# Filtre_Seulement.net
KiCad netlist of a schematic drawn in Altium Designer
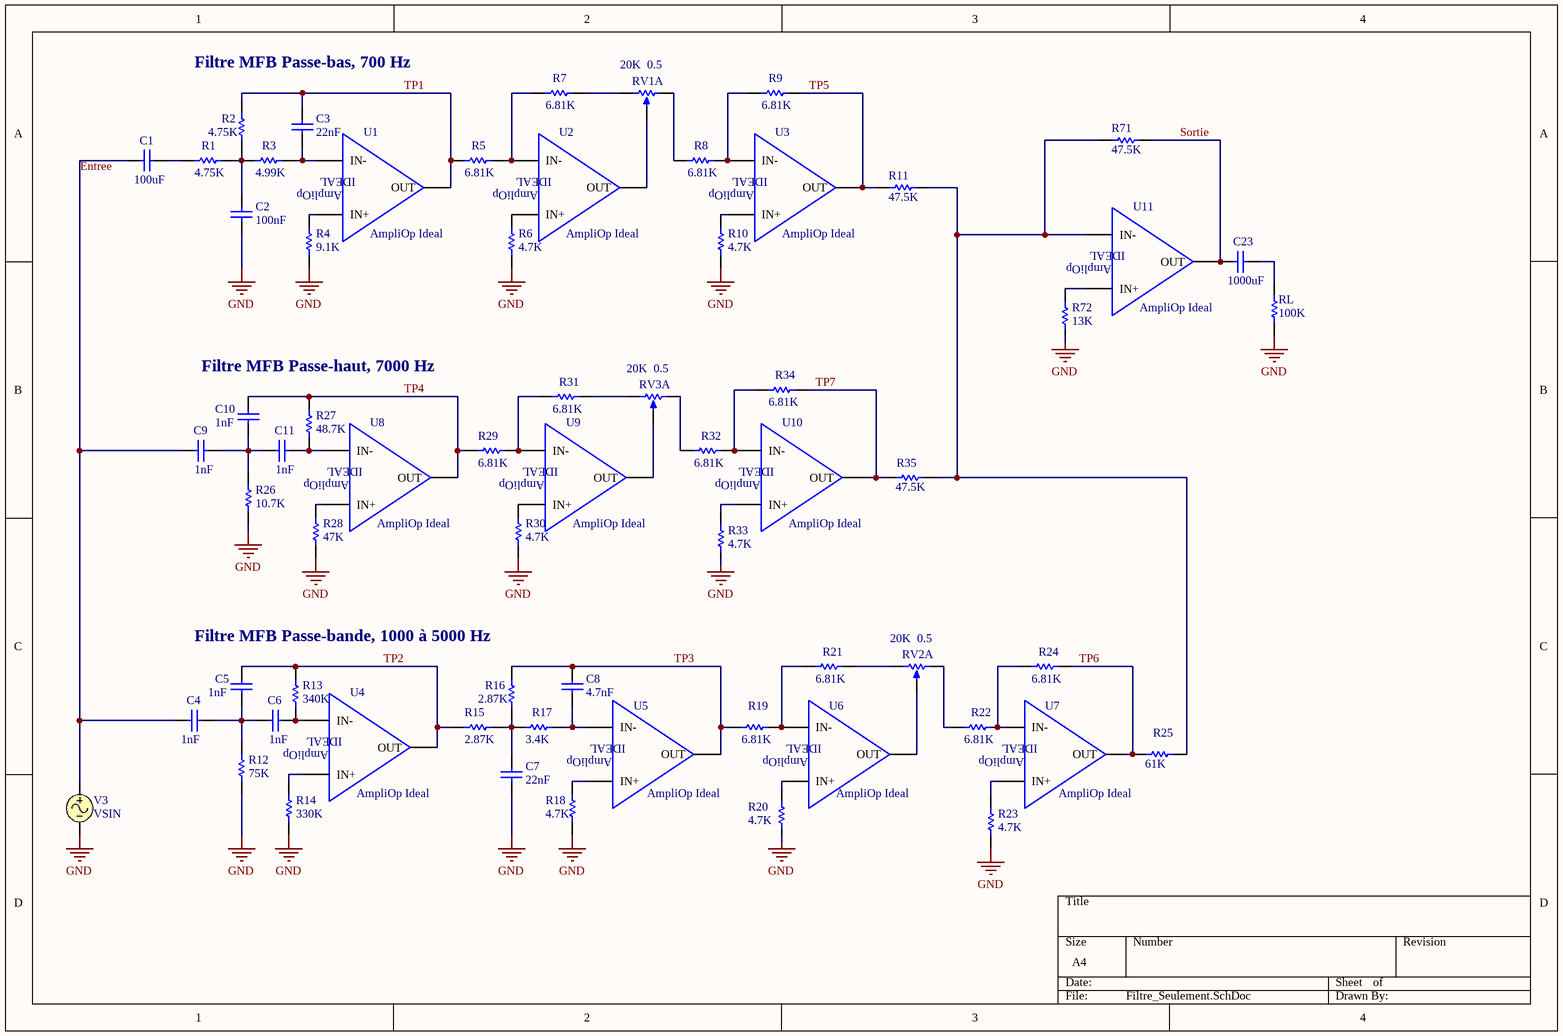
[diagram p0: Filtre_Seulement.SchDoc]

(export (version "E")
  (design (tool "Eeschema 10.0.6"))
  (components
    (comp (ref "C1")
      (value "100uF")
      (footprint "RAD-0.3")
      (description "Capacitor")
      (fields (field (name "Comment") "Cap") (field (name "PUBLISHER") "Altium Limited"))
      (libsource (lib "Miscellaneous Devices") (part "Cap"))
    )
    (comp (ref "C2")
      (value "100nF")
      (footprint "RAD-0.3")
      (description "Capacitor")
      (fields (field (name "Comment") "Cap") (field (name "PUBLISHER") "Altium Limited"))
      (libsource (lib "Miscellaneous Devices") (part "Cap"))
    )
    (comp (ref "C3")
      (value "22nF")
      (footprint "RAD-0.3")
      (description "Capacitor")
      (fields (field (name "Comment") "Cap") (field (name "PUBLISHER") "Altium Limited"))
      (libsource (lib "Miscellaneous Devices") (part "Cap"))
    )
    (comp (ref "C4")
      (value "1nF")
      (footprint "RAD-0.3")
      (description "Capacitor")
      (fields (field (name "Comment") "Cap") (field (name "PUBLISHER") "Altium Limited"))
      (libsource (lib "Miscellaneous Devices") (part "Cap"))
    )
    (comp (ref "C5")
      (value "1nF")
      (footprint "RAD-0.3")
      (description "Capacitor")
      (fields (field (name "Comment") "Cap") (field (name "PUBLISHER") "Altium Limited"))
      (libsource (lib "Miscellaneous Devices") (part "Cap"))
    )
    (comp (ref "C6")
      (value "1nF")
      (footprint "RAD-0.3")
      (description "Capacitor")
      (fields (field (name "Comment") "Cap") (field (name "PUBLISHER") "Altium Limited"))
      (libsource (lib "Miscellaneous Devices") (part "Cap"))
    )
    (comp (ref "C7")
      (value "22nF")
      (footprint "RAD-0.3")
      (description "Capacitor")
      (fields (field (name "Comment") "Cap") (field (name "PUBLISHER") "Altium Limited"))
      (libsource (lib "Miscellaneous Devices") (part "Cap"))
    )
    (comp (ref "C8")
      (value "4.7nF")
      (footprint "RAD-0.3")
      (description "Capacitor")
      (fields (field (name "Comment") "Cap") (field (name "PUBLISHER") "Altium Limited"))
      (libsource (lib "Miscellaneous Devices") (part "Cap"))
    )
    (comp (ref "C9")
      (value "1nF")
      (footprint "RAD-0.3")
      (description "Capacitor")
      (fields (field (name "Comment") "Cap") (field (name "PUBLISHER") "Altium Limited"))
      (libsource (lib "Miscellaneous Devices") (part "Cap"))
    )
    (comp (ref "C10")
      (value "1nF")
      (footprint "RAD-0.3")
      (description "Capacitor")
      (fields (field (name "Comment") "Cap") (field (name "PUBLISHER") "Altium Limited"))
      (libsource (lib "Miscellaneous Devices") (part "Cap"))
    )
    (comp (ref "C11")
      (value "1nF")
      (footprint "RAD-0.3")
      (description "Capacitor")
      (fields (field (name "Comment") "Cap") (field (name "PUBLISHER") "Altium Limited"))
      (libsource (lib "Miscellaneous Devices") (part "Cap"))
    )
    (comp (ref "C23")
      (value "1000uF")
      (footprint "RAD-0.3")
      (description "Capacitor")
      (fields (field (name "Comment") "Cap") (field (name "PUBLISHER") "Altium Limited"))
      (libsource (lib "Miscellaneous Devices") (part "Cap"))
    )
    (comp (ref "R1")
      (value "4.75K")
      (footprint "AXIAL-0.3")
      (description "Resistor")
      (fields (field (name "Comment") "Res1") (field (name "PUBLISHER") "Altium Limited"))
      (libsource (lib "Miscellaneous Devices") (part "Res1"))
    )
    (comp (ref "R2")
      (value "4.75K")
      (footprint "AXIAL-0.3")
      (description "Resistor")
      (fields (field (name "Comment") "Res1") (field (name "PUBLISHER") "Altium Limited"))
      (libsource (lib "Miscellaneous Devices") (part "Res1"))
    )
    (comp (ref "R3")
      (value "4.99K")
      (footprint "AXIAL-0.3")
      (description "Resistor")
      (fields (field (name "Comment") "Res1") (field (name "PUBLISHER") "Altium Limited"))
      (libsource (lib "Miscellaneous Devices") (part "Res1"))
    )
    (comp (ref "R4")
      (value "9.1K")
      (footprint "AXIAL-0.3")
      (description "Resistor")
      (fields (field (name "Comment") "Res1") (field (name "PUBLISHER") "Altium Limited"))
      (libsource (lib "Miscellaneous Devices") (part "Res1"))
    )
    (comp (ref "R5")
      (value "6.81K")
      (footprint "AXIAL-0.3")
      (description "Resistor")
      (fields (field (name "Comment") "Res1") (field (name "PUBLISHER") "Altium Limited"))
      (libsource (lib "Miscellaneous Devices") (part "Res1"))
    )
    (comp (ref "R6")
      (value "4.7K")
      (footprint "AXIAL-0.3")
      (description "Resistor")
      (fields (field (name "Comment") "Res1") (field (name "PUBLISHER") "Altium Limited"))
      (libsource (lib "Miscellaneous Devices") (part "Res1"))
    )
    (comp (ref "R7")
      (value "6.81K")
      (footprint "AXIAL-0.3")
      (description "Resistor")
      (fields (field (name "Comment") "Res1") (field (name "PUBLISHER") "Altium Limited"))
      (libsource (lib "Miscellaneous Devices") (part "Res1"))
    )
    (comp (ref "R8")
      (value "6.81K")
      (footprint "AXIAL-0.3")
      (description "Resistor")
      (fields (field (name "Comment") "Res1") (field (name "PUBLISHER") "Altium Limited"))
      (libsource (lib "Miscellaneous Devices") (part "Res1"))
    )
    (comp (ref "R9")
      (value "6.81K")
      (footprint "AXIAL-0.3")
      (description "Resistor")
      (fields (field (name "Comment") "Res1") (field (name "PUBLISHER") "Altium Limited"))
      (libsource (lib "Miscellaneous Devices") (part "Res1"))
    )
    (comp (ref "R10")
      (value "4.7K")
      (footprint "AXIAL-0.3")
      (description "Resistor")
      (fields (field (name "Comment") "Res1") (field (name "PUBLISHER") "Altium Limited"))
      (libsource (lib "Miscellaneous Devices") (part "Res1"))
    )
    (comp (ref "R11")
      (value "47.5K")
      (footprint "AXIAL-0.3")
      (description "Resistor")
      (fields (field (name "Comment") "Res1") (field (name "PUBLISHER") "Altium Limited"))
      (libsource (lib "Miscellaneous Devices") (part "Res1"))
    )
    (comp (ref "R12")
      (value "75K")
      (footprint "AXIAL-0.3")
      (description "Resistor")
      (fields (field (name "Comment") "Res1") (field (name "PUBLISHER") "Altium Limited"))
      (libsource (lib "Miscellaneous Devices") (part "Res1"))
    )
    (comp (ref "R13")
      (value "340K")
      (footprint "AXIAL-0.3")
      (description "Resistor")
      (fields (field (name "Comment") "Res1") (field (name "PUBLISHER") "Altium Limited"))
      (libsource (lib "Miscellaneous Devices") (part "Res1"))
    )
    (comp (ref "R14")
      (value "330K")
      (footprint "AXIAL-0.3")
      (description "Resistor")
      (fields (field (name "Comment") "Res1") (field (name "PUBLISHER") "Altium Limited"))
      (libsource (lib "Miscellaneous Devices") (part "Res1"))
    )
    (comp (ref "R15")
      (value "2.87K")
      (footprint "AXIAL-0.3")
      (description "Resistor")
      (fields (field (name "Comment") "Res1") (field (name "PUBLISHER") "Altium Limited"))
      (libsource (lib "Miscellaneous Devices") (part "Res1"))
    )
    (comp (ref "R16")
      (value "2.87K")
      (footprint "AXIAL-0.3")
      (description "Resistor")
      (fields (field (name "Comment") "Res1") (field (name "PUBLISHER") "Altium Limited"))
      (libsource (lib "Miscellaneous Devices") (part "Res1"))
    )
    (comp (ref "R17")
      (value "3.4K")
      (footprint "AXIAL-0.3")
      (description "Resistor")
      (fields (field (name "Comment") "Res1") (field (name "PUBLISHER") "Altium Limited"))
      (libsource (lib "Miscellaneous Devices") (part "Res1"))
    )
    (comp (ref "R18")
      (value "4.7K")
      (footprint "AXIAL-0.3")
      (description "Resistor")
      (fields (field (name "Comment") "Res1") (field (name "PUBLISHER") "Altium Limited"))
      (libsource (lib "Miscellaneous Devices") (part "Res1"))
    )
    (comp (ref "R19")
      (value "6.81K")
      (footprint "AXIAL-0.3")
      (description "Resistor")
      (fields (field (name "Comment") "Res1") (field (name "PUBLISHER") "Altium Limited"))
      (libsource (lib "Miscellaneous Devices") (part "Res1"))
    )
    (comp (ref "R20")
      (value "4.7K")
      (footprint "AXIAL-0.3")
      (description "Resistor")
      (fields (field (name "Comment") "Res1") (field (name "PUBLISHER") "Altium Limited"))
      (libsource (lib "Miscellaneous Devices") (part "Res1"))
    )
    (comp (ref "R21")
      (value "6.81K")
      (footprint "AXIAL-0.3")
      (description "Resistor")
      (fields (field (name "Comment") "Res1") (field (name "PUBLISHER") "Altium Limited"))
      (libsource (lib "Miscellaneous Devices") (part "Res1"))
    )
    (comp (ref "R22")
      (value "6.81K")
      (footprint "AXIAL-0.3")
      (description "Resistor")
      (fields (field (name "Comment") "Res1") (field (name "PUBLISHER") "Altium Limited"))
      (libsource (lib "Miscellaneous Devices") (part "Res1"))
    )
    (comp (ref "R23")
      (value "4.7K")
      (footprint "AXIAL-0.3")
      (description "Resistor")
      (fields (field (name "Comment") "Res1") (field (name "PUBLISHER") "Altium Limited"))
      (libsource (lib "Miscellaneous Devices") (part "Res1"))
    )
    (comp (ref "R24")
      (value "6.81K")
      (footprint "AXIAL-0.3")
      (description "Resistor")
      (fields (field (name "Comment") "Res1") (field (name "PUBLISHER") "Altium Limited"))
      (libsource (lib "Miscellaneous Devices") (part "Res1"))
    )
    (comp (ref "R25")
      (value "61K")
      (footprint "AXIAL-0.3")
      (description "Resistor")
      (fields (field (name "Comment") "Res1") (field (name "PUBLISHER") "Altium Limited"))
      (libsource (lib "Miscellaneous Devices") (part "Res1"))
    )
    (comp (ref "R26")
      (value "10.7K")
      (footprint "AXIAL-0.3")
      (description "Resistor")
      (fields (field (name "Comment") "Res1") (field (name "PUBLISHER") "Altium Limited"))
      (libsource (lib "Miscellaneous Devices") (part "Res1"))
    )
    (comp (ref "R27")
      (value "48.7K")
      (footprint "AXIAL-0.3")
      (description "Resistor")
      (fields (field (name "Comment") "Res1") (field (name "PUBLISHER") "Altium Limited"))
      (libsource (lib "Miscellaneous Devices") (part "Res1"))
    )
    (comp (ref "R28")
      (value "47K")
      (footprint "AXIAL-0.3")
      (description "Resistor")
      (fields (field (name "Comment") "Res1") (field (name "PUBLISHER") "Altium Limited"))
      (libsource (lib "Miscellaneous Devices") (part "Res1"))
    )
    (comp (ref "R29")
      (value "6.81K")
      (footprint "AXIAL-0.3")
      (description "Resistor")
      (fields (field (name "Comment") "Res1") (field (name "PUBLISHER") "Altium Limited"))
      (libsource (lib "Miscellaneous Devices") (part "Res1"))
    )
    (comp (ref "R30")
      (value "4.7K")
      (footprint "AXIAL-0.3")
      (description "Resistor")
      (fields (field (name "Comment") "Res1") (field (name "PUBLISHER") "Altium Limited"))
      (libsource (lib "Miscellaneous Devices") (part "Res1"))
    )
    (comp (ref "R31")
      (value "6.81K")
      (footprint "AXIAL-0.3")
      (description "Resistor")
      (fields (field (name "Comment") "Res1") (field (name "PUBLISHER") "Altium Limited"))
      (libsource (lib "Miscellaneous Devices") (part "Res1"))
    )
    (comp (ref "R32")
      (value "6.81K")
      (footprint "AXIAL-0.3")
      (description "Resistor")
      (fields (field (name "Comment") "Res1") (field (name "PUBLISHER") "Altium Limited"))
      (libsource (lib "Miscellaneous Devices") (part "Res1"))
    )
    (comp (ref "R33")
      (value "4.7K")
      (footprint "AXIAL-0.3")
      (description "Resistor")
      (fields (field (name "Comment") "Res1") (field (name "PUBLISHER") "Altium Limited"))
      (libsource (lib "Miscellaneous Devices") (part "Res1"))
    )
    (comp (ref "R34")
      (value "6.81K")
      (footprint "AXIAL-0.3")
      (description "Resistor")
      (fields (field (name "Comment") "Res1") (field (name "PUBLISHER") "Altium Limited"))
      (libsource (lib "Miscellaneous Devices") (part "Res1"))
    )
    (comp (ref "R35")
      (value "47.5K")
      (footprint "AXIAL-0.3")
      (description "Resistor")
      (fields (field (name "Comment") "Res1") (field (name "PUBLISHER") "Altium Limited"))
      (libsource (lib "Miscellaneous Devices") (part "Res1"))
    )
    (comp (ref "R71")
      (value "47.5K")
      (footprint "AXIAL-0.3")
      (description "Resistor")
      (fields (field (name "Comment") "Res1") (field (name "PUBLISHER") "Altium Limited"))
      (libsource (lib "Miscellaneous Devices") (part "Res1"))
    )
    (comp (ref "R72")
      (value "13K")
      (footprint "AXIAL-0.3")
      (description "Resistor")
      (fields (field (name "Comment") "Res1") (field (name "PUBLISHER") "Altium Limited"))
      (libsource (lib "Miscellaneous Devices") (part "Res1"))
    )
    (comp (ref "RL")
      (value "100K")
      (footprint "AXIAL-0.3")
      (description "Resistor")
      (fields (field (name "Comment") "Res1") (field (name "PUBLISHER") "Altium Limited"))
      (libsource (lib "Miscellaneous Devices") (part "Res1"))
    )
    (comp (ref "RV1A")
      (value "20K")
      (footprint "VR5")
      (description "Potentiometer")
      (fields
        (field (name "SET POSITION") "0.5")
        (field (name "Comment") "RPot")
        (field (name "PUBLISHER") "Altium Limited")
      )
      (libsource (lib "Miscellaneous Devices") (part "RPot"))
    )
    (comp (ref "RV2A")
      (value "20K")
      (footprint "VR5")
      (description "Potentiometer")
      (fields
        (field (name "SET POSITION") "0.5")
        (field (name "Comment") "RPot")
        (field (name "PUBLISHER") "Altium Limited")
      )
      (libsource (lib "Miscellaneous Devices") (part "RPot"))
    )
    (comp (ref "RV3A")
      (value "20K")
      (footprint "VR5")
      (description "Potentiometer")
      (fields
        (field (name "SET POSITION") "0.5")
        (field (name "Comment") "RPot")
        (field (name "PUBLISHER") "Altium Limited")
      )
      (libsource (lib "Miscellaneous Devices") (part "RPot"))
    )
    (comp (ref "U1") (value "AmpliOp Ideal") (libsource (lib "Librarie_S2") (part "AmpliOp_ideal")))
    (comp (ref "U2") (value "AmpliOp Ideal") (libsource (lib "Librarie_S2") (part "AmpliOp_ideal")))
    (comp (ref "U3") (value "AmpliOp Ideal") (libsource (lib "Librarie_S2") (part "AmpliOp_ideal")))
    (comp (ref "U4") (value "AmpliOp Ideal") (libsource (lib "Librarie_S2") (part "AmpliOp_ideal")))
    (comp (ref "U5") (value "AmpliOp Ideal") (libsource (lib "Librarie_S2") (part "AmpliOp_ideal")))
    (comp (ref "U6") (value "AmpliOp Ideal") (libsource (lib "Librarie_S2") (part "AmpliOp_ideal")))
    (comp (ref "U7") (value "AmpliOp Ideal") (libsource (lib "Librarie_S2") (part "AmpliOp_ideal")))
    (comp (ref "U8") (value "AmpliOp Ideal") (libsource (lib "Librarie_S2") (part "AmpliOp_ideal")))
    (comp (ref "U9") (value "AmpliOp Ideal") (libsource (lib "Librarie_S2") (part "AmpliOp_ideal")))
    (comp (ref "U10") (value "AmpliOp Ideal") (libsource (lib "Librarie_S2") (part "AmpliOp_ideal")))
    (comp (ref "U11") (value "AmpliOp Ideal") (libsource (lib "Librarie_S2") (part "AmpliOp_ideal")))
    (comp (ref "V3")
      (value "VSIN")
      (description "Sinusoidal Voltage Source")
      (fields (field (name "PUBLISHER") "Altium Limited"))
      (libsource (lib "Simulation Sources") (part "VSIN"))
    )
  )
  (nets
    (net (code "1") (name "/Entree") (class "Default")
      (node (ref "C1") (pin "1") (pinfunction "1_1") (pintype "passive"))
      (node (ref "C4") (pin "1") (pinfunction "1_1") (pintype "passive"))
      (node (ref "C9") (pin "1") (pinfunction "1_1") (pintype "passive"))
      (node (ref "V3") (pin "1") (pinfunction "1_1") (pintype "passive"))
    )
    (net (code "2") (name "/Sortie") (class "Default")
      (node (ref "C23") (pin "1") (pinfunction "1_1") (pintype "passive"))
      (node (ref "R71") (pin "2") (pinfunction "2_2") (pintype "passive"))
      (node (ref "U11") (pin "3") (pinfunction "OUT_3") (pintype "passive"))
    )
    (net (code "3") (name "/TP1") (class "Default")
      (node (ref "C3") (pin "1") (pinfunction "1_1") (pintype "passive"))
      (node (ref "R2") (pin "1") (pinfunction "1_1") (pintype "passive"))
      (node (ref "R5") (pin "1") (pinfunction "1_1") (pintype "passive"))
      (node (ref "U1") (pin "3") (pinfunction "OUT_3") (pintype "passive"))
    )
    (net (code "4") (name "/TP2") (class "Default")
      (node (ref "C5") (pin "1") (pinfunction "1_1") (pintype "passive"))
      (node (ref "R13") (pin "1") (pinfunction "1_1") (pintype "passive"))
      (node (ref "R15") (pin "1") (pinfunction "1_1") (pintype "passive"))
      (node (ref "U4") (pin "3") (pinfunction "OUT_3") (pintype "passive"))
    )
    (net (code "5") (name "/TP3") (class "Default")
      (node (ref "C8") (pin "1") (pinfunction "1_1") (pintype "passive"))
      (node (ref "R16") (pin "1") (pinfunction "1_1") (pintype "passive"))
      (node (ref "R19") (pin "1") (pinfunction "1_1") (pintype "passive"))
      (node (ref "U5") (pin "3") (pinfunction "OUT_3") (pintype "passive"))
    )
    (net (code "6") (name "/TP4") (class "Default")
      (node (ref "C10") (pin "1") (pinfunction "1_1") (pintype "passive"))
      (node (ref "R27") (pin "1") (pinfunction "1_1") (pintype "passive"))
      (node (ref "R29") (pin "1") (pinfunction "1_1") (pintype "passive"))
      (node (ref "U8") (pin "3") (pinfunction "OUT_3") (pintype "passive"))
    )
    (net (code "7") (name "/TP5") (class "Default")
      (node (ref "R11") (pin "1") (pinfunction "1_1") (pintype "passive"))
      (node (ref "R9") (pin "2") (pinfunction "2_2") (pintype "passive"))
      (node (ref "U3") (pin "3") (pinfunction "OUT_3") (pintype "passive"))
    )
    (net (code "8") (name "/TP6") (class "Default")
      (node (ref "R24") (pin "2") (pinfunction "2_2") (pintype "passive"))
      (node (ref "R25") (pin "1") (pinfunction "1_1") (pintype "passive"))
      (node (ref "U7") (pin "3") (pinfunction "OUT_3") (pintype "passive"))
    )
    (net (code "9") (name "/TP7") (class "Default")
      (node (ref "R34") (pin "2") (pinfunction "2_2") (pintype "passive"))
      (node (ref "R35") (pin "1") (pinfunction "1_1") (pintype "passive"))
      (node (ref "U10") (pin "3") (pinfunction "OUT_3") (pintype "passive"))
    )
    (net (code "10") (name "GND") (class "Default")
      (node (ref "C2") (pin "2") (pinfunction "2_2") (pintype "passive"))
      (node (ref "C7") (pin "2") (pinfunction "2_2") (pintype "passive"))
      (node (ref "R10") (pin "2") (pinfunction "2_2") (pintype "passive"))
      (node (ref "R12") (pin "2") (pinfunction "2_2") (pintype "passive"))
      (node (ref "R14") (pin "2") (pinfunction "2_2") (pintype "passive"))
      (node (ref "R18") (pin "2") (pinfunction "2_2") (pintype "passive"))
      (node (ref "R20") (pin "2") (pinfunction "2_2") (pintype "passive"))
      (node (ref "R23") (pin "2") (pinfunction "2_2") (pintype "passive"))
      (node (ref "R26") (pin "2") (pinfunction "2_2") (pintype "passive"))
      (node (ref "R28") (pin "2") (pinfunction "2_2") (pintype "passive"))
      (node (ref "R30") (pin "2") (pinfunction "2_2") (pintype "passive"))
      (node (ref "R33") (pin "2") (pinfunction "2_2") (pintype "passive"))
      (node (ref "R4") (pin "2") (pinfunction "2_2") (pintype "passive"))
      (node (ref "R6") (pin "2") (pinfunction "2_2") (pintype "passive"))
      (node (ref "R72") (pin "2") (pinfunction "2_2") (pintype "passive"))
      (node (ref "RL") (pin "1") (pinfunction "1_1") (pintype "passive"))
      (node (ref "V3") (pin "2") (pinfunction "2_2") (pintype "passive"))
    )
    (net (code "11") (name "Net-(C1-Pad2)") (class "Default")
      (node (ref "C1") (pin "2") (pinfunction "2_2") (pintype "passive"))
      (node (ref "R1") (pin "1") (pinfunction "1_1") (pintype "passive"))
    )
    (net (code "12") (name "Net-(C2-Pad1)") (class "Default")
      (node (ref "C2") (pin "1") (pinfunction "1_1") (pintype "passive"))
      (node (ref "R1") (pin "2") (pinfunction "2_2") (pintype "passive"))
      (node (ref "R2") (pin "2") (pinfunction "2_2") (pintype "passive"))
      (node (ref "R3") (pin "1") (pinfunction "1_1") (pintype "passive"))
    )
    (net (code "13") (name "Net-(C4-Pad2)") (class "Default")
      (node (ref "C4") (pin "2") (pinfunction "2_2") (pintype "passive"))
      (node (ref "C5") (pin "2") (pinfunction "2_2") (pintype "passive"))
      (node (ref "C6") (pin "1") (pinfunction "1_1") (pintype "passive"))
      (node (ref "R12") (pin "1") (pinfunction "1_1") (pintype "passive"))
    )
    (net (code "14") (name "Net-(C7-Pad1)") (class "Default")
      (node (ref "C7") (pin "1") (pinfunction "1_1") (pintype "passive"))
      (node (ref "R15") (pin "2") (pinfunction "2_2") (pintype "passive"))
      (node (ref "R16") (pin "2") (pinfunction "2_2") (pintype "passive"))
      (node (ref "R17") (pin "1") (pinfunction "1_1") (pintype "passive"))
    )
    (net (code "15") (name "Net-(C10-Pad2)") (class "Default")
      (node (ref "C10") (pin "2") (pinfunction "2_2") (pintype "passive"))
      (node (ref "C11") (pin "1") (pinfunction "1_1") (pintype "passive"))
      (node (ref "C9") (pin "2") (pinfunction "2_2") (pintype "passive"))
      (node (ref "R26") (pin "1") (pinfunction "1_1") (pintype "passive"))
    )
    (net (code "16") (name "Net-(C23-Pad2)") (class "Default")
      (node (ref "C23") (pin "2") (pinfunction "2_2") (pintype "passive"))
      (node (ref "RL") (pin "2") (pinfunction "2_2") (pintype "passive"))
    )
    (net (code "17") (name "Net-(RV1A-BOT)") (class "Default")
      (node (ref "R8") (pin "1") (pinfunction "1_1") (pintype "passive"))
      (node (ref "RV1A") (pin "2") (pinfunction "BOT_2") (pintype "passive"))
    )
    (net (code "18") (name "Net-(RV1A-TAP)") (class "Default")
      (node (ref "RV1A") (pin "3") (pinfunction "TAP_3") (pintype "passive"))
      (node (ref "U2") (pin "3") (pinfunction "OUT_3") (pintype "passive"))
    )
    (net (code "19") (name "Net-(RV1A-TOP)") (class "Default")
      (node (ref "R7") (pin "2") (pinfunction "2_2") (pintype "passive"))
      (node (ref "RV1A") (pin "1") (pinfunction "TOP_1") (pintype "passive"))
    )
    (net (code "20") (name "Net-(RV2A-BOT)") (class "Default")
      (node (ref "R22") (pin "1") (pinfunction "1_1") (pintype "passive"))
      (node (ref "RV2A") (pin "2") (pinfunction "BOT_2") (pintype "passive"))
    )
    (net (code "21") (name "Net-(RV2A-TAP)") (class "Default")
      (node (ref "RV2A") (pin "3") (pinfunction "TAP_3") (pintype "passive"))
      (node (ref "U6") (pin "3") (pinfunction "OUT_3") (pintype "passive"))
    )
    (net (code "22") (name "Net-(RV2A-TOP)") (class "Default")
      (node (ref "R21") (pin "2") (pinfunction "2_2") (pintype "passive"))
      (node (ref "RV2A") (pin "1") (pinfunction "TOP_1") (pintype "passive"))
    )
    (net (code "23") (name "Net-(RV3A-BOT)") (class "Default")
      (node (ref "R32") (pin "1") (pinfunction "1_1") (pintype "passive"))
      (node (ref "RV3A") (pin "2") (pinfunction "BOT_2") (pintype "passive"))
    )
    (net (code "24") (name "Net-(RV3A-TAP)") (class "Default")
      (node (ref "RV3A") (pin "3") (pinfunction "TAP_3") (pintype "passive"))
      (node (ref "U9") (pin "3") (pinfunction "OUT_3") (pintype "passive"))
    )
    (net (code "25") (name "Net-(RV3A-TOP)") (class "Default")
      (node (ref "R31") (pin "2") (pinfunction "2_2") (pintype "passive"))
      (node (ref "RV3A") (pin "1") (pinfunction "TOP_1") (pintype "passive"))
    )
    (net (code "26") (name "Net-(U1-IN+)") (class "Default")
      (node (ref "R4") (pin "1") (pinfunction "1_1") (pintype "passive"))
      (node (ref "U1") (pin "1") (pinfunction "IN+_1") (pintype "passive"))
    )
    (net (code "27") (name "Net-(U1-IN-)") (class "Default")
      (node (ref "C3") (pin "2") (pinfunction "2_2") (pintype "passive"))
      (node (ref "R3") (pin "2") (pinfunction "2_2") (pintype "passive"))
      (node (ref "U1") (pin "2") (pinfunction "IN-_2") (pintype "passive"))
    )
    (net (code "28") (name "Net-(U2-IN+)") (class "Default")
      (node (ref "R6") (pin "1") (pinfunction "1_1") (pintype "passive"))
      (node (ref "U2") (pin "1") (pinfunction "IN+_1") (pintype "passive"))
    )
    (net (code "29") (name "Net-(U2-IN-)") (class "Default")
      (node (ref "R5") (pin "2") (pinfunction "2_2") (pintype "passive"))
      (node (ref "R7") (pin "1") (pinfunction "1_1") (pintype "passive"))
      (node (ref "U2") (pin "2") (pinfunction "IN-_2") (pintype "passive"))
    )
    (net (code "30") (name "Net-(U3-IN+)") (class "Default")
      (node (ref "R10") (pin "1") (pinfunction "1_1") (pintype "passive"))
      (node (ref "U3") (pin "1") (pinfunction "IN+_1") (pintype "passive"))
    )
    (net (code "31") (name "Net-(U3-IN-)") (class "Default")
      (node (ref "R8") (pin "2") (pinfunction "2_2") (pintype "passive"))
      (node (ref "R9") (pin "1") (pinfunction "1_1") (pintype "passive"))
      (node (ref "U3") (pin "2") (pinfunction "IN-_2") (pintype "passive"))
    )
    (net (code "32") (name "Net-(U4-IN+)") (class "Default")
      (node (ref "R14") (pin "1") (pinfunction "1_1") (pintype "passive"))
      (node (ref "U4") (pin "1") (pinfunction "IN+_1") (pintype "passive"))
    )
    (net (code "33") (name "Net-(U4-IN-)") (class "Default")
      (node (ref "C6") (pin "2") (pinfunction "2_2") (pintype "passive"))
      (node (ref "R13") (pin "2") (pinfunction "2_2") (pintype "passive"))
      (node (ref "U4") (pin "2") (pinfunction "IN-_2") (pintype "passive"))
    )
    (net (code "34") (name "Net-(U5-IN+)") (class "Default")
      (node (ref "R18") (pin "1") (pinfunction "1_1") (pintype "passive"))
      (node (ref "U5") (pin "1") (pinfunction "IN+_1") (pintype "passive"))
    )
    (net (code "35") (name "Net-(U5-IN-)") (class "Default")
      (node (ref "C8") (pin "2") (pinfunction "2_2") (pintype "passive"))
      (node (ref "R17") (pin "2") (pinfunction "2_2") (pintype "passive"))
      (node (ref "U5") (pin "2") (pinfunction "IN-_2") (pintype "passive"))
    )
    (net (code "36") (name "Net-(U6-IN+)") (class "Default")
      (node (ref "R20") (pin "1") (pinfunction "1_1") (pintype "passive"))
      (node (ref "U6") (pin "1") (pinfunction "IN+_1") (pintype "passive"))
    )
    (net (code "37") (name "Net-(U6-IN-)") (class "Default")
      (node (ref "R19") (pin "2") (pinfunction "2_2") (pintype "passive"))
      (node (ref "R21") (pin "1") (pinfunction "1_1") (pintype "passive"))
      (node (ref "U6") (pin "2") (pinfunction "IN-_2") (pintype "passive"))
    )
    (net (code "38") (name "Net-(U7-IN+)") (class "Default")
      (node (ref "R23") (pin "1") (pinfunction "1_1") (pintype "passive"))
      (node (ref "U7") (pin "1") (pinfunction "IN+_1") (pintype "passive"))
    )
    (net (code "39") (name "Net-(U7-IN-)") (class "Default")
      (node (ref "R22") (pin "2") (pinfunction "2_2") (pintype "passive"))
      (node (ref "R24") (pin "1") (pinfunction "1_1") (pintype "passive"))
      (node (ref "U7") (pin "2") (pinfunction "IN-_2") (pintype "passive"))
    )
    (net (code "40") (name "Net-(U8-IN+)") (class "Default")
      (node (ref "R28") (pin "1") (pinfunction "1_1") (pintype "passive"))
      (node (ref "U8") (pin "1") (pinfunction "IN+_1") (pintype "passive"))
    )
    (net (code "41") (name "Net-(U8-IN-)") (class "Default")
      (node (ref "C11") (pin "2") (pinfunction "2_2") (pintype "passive"))
      (node (ref "R27") (pin "2") (pinfunction "2_2") (pintype "passive"))
      (node (ref "U8") (pin "2") (pinfunction "IN-_2") (pintype "passive"))
    )
    (net (code "42") (name "Net-(U9-IN+)") (class "Default")
      (node (ref "R30") (pin "1") (pinfunction "1_1") (pintype "passive"))
      (node (ref "U9") (pin "1") (pinfunction "IN+_1") (pintype "passive"))
    )
    (net (code "43") (name "Net-(U9-IN-)") (class "Default")
      (node (ref "R29") (pin "2") (pinfunction "2_2") (pintype "passive"))
      (node (ref "R31") (pin "1") (pinfunction "1_1") (pintype "passive"))
      (node (ref "U9") (pin "2") (pinfunction "IN-_2") (pintype "passive"))
    )
    (net (code "44") (name "Net-(U10-IN+)") (class "Default")
      (node (ref "R33") (pin "1") (pinfunction "1_1") (pintype "passive"))
      (node (ref "U10") (pin "1") (pinfunction "IN+_1") (pintype "passive"))
    )
    (net (code "45") (name "Net-(U10-IN-)") (class "Default")
      (node (ref "R32") (pin "2") (pinfunction "2_2") (pintype "passive"))
      (node (ref "R34") (pin "1") (pinfunction "1_1") (pintype "passive"))
      (node (ref "U10") (pin "2") (pinfunction "IN-_2") (pintype "passive"))
    )
    (net (code "46") (name "Net-(U11-IN+)") (class "Default")
      (node (ref "R72") (pin "1") (pinfunction "1_1") (pintype "passive"))
      (node (ref "U11") (pin "1") (pinfunction "IN+_1") (pintype "passive"))
    )
    (net (code "47") (name "Net-(U11-IN-)") (class "Default")
      (node (ref "R11") (pin "2") (pinfunction "2_2") (pintype "passive"))
      (node (ref "R25") (pin "2") (pinfunction "2_2") (pintype "passive"))
      (node (ref "R35") (pin "2") (pinfunction "2_2") (pintype "passive"))
      (node (ref "R71") (pin "1") (pinfunction "1_1") (pintype "passive"))
      (node (ref "U11") (pin "2") (pinfunction "IN-_2") (pintype "passive"))
    )
  )
)
